# CurrentSense.net
KiCad netlist of a schematic drawn in Altium Designer
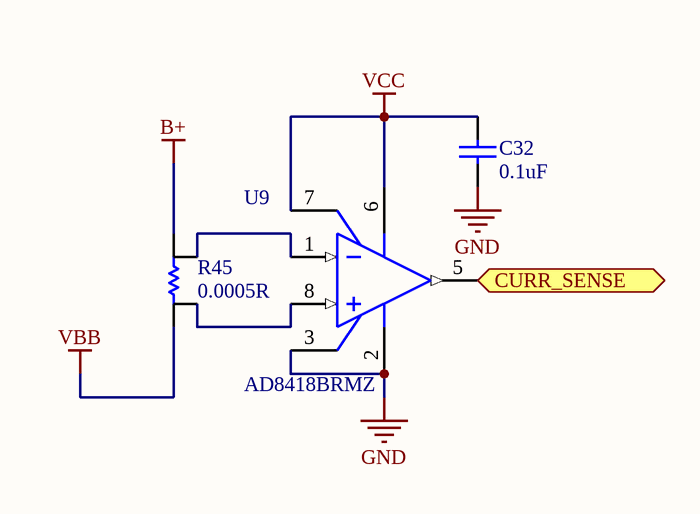
[diagram p0: CurrentSense.SchDoc]

(export (version "E")
  (design (tool "Eeschema 10.0.6"))
  (components
    (comp (ref "C32")
      (value "0.1uF")
      (footprint "C0402[1005X55]")
      (description "0.1uF 6.3V 10% 0402 (1005 Metric)")
      (fields (field (name "TOLERANCE") "10%") (field (name "PARTNUMBER") "GRM155R70J104KA01D"))
      (libsource (lib "Capacitors") (part "CAP_0.1uF_6.3V_0402_10%"))
    )
    (comp (ref "R45")
      (value "0.0005R")
      (footprint "WSL2726")
      (description "Current Sense Resistor, 0.0005R")
      (fields (field (name "PARTNUMBER") "WSLP2726L5000FEA") (field (name "MANUFACTURER") "Vishay / Dale"))
      (libsource (lib "Components") (part "WSLP2726"))
    )
    (comp (ref "U9")
      (value "AD8418BRMZ")
      (footprint "MSOP-8")
      (description "Current Sense Amplifiers Zero Drift ,Precision Current Sense AMP")
      (fields (field (name "MANUFACTURER") "Analog Devices"))
      (libsource (lib "ICs") (part "AD8418BRMZ"))
    )
  )
  (nets
    (net (code "1") (name "/CURR_SENSE") (class "Default")
      (node (ref "U9") (pin "5") (pinfunction "OUT_5") (pintype "output"))
    )
    (net (code "2") (name "B+") (class "Default")
      (node (ref "R45") (pin "2") (pinfunction "2_2") (pintype "passive"))
    )
    (net (code "3") (name "GND") (class "Default")
      (node (ref "C32") (pin "1") (pinfunction "1_1") (pintype "passive"))
      (node (ref "U9") (pin "2") (pinfunction "GND_2") (pintype "power_in"))
      (node (ref "U9") (pin "3") (pinfunction "VREF2_3") (pintype "passive"))
    )
    (net (code "4") (name "Net-(U9-IN+)") (class "Default")
      (node (ref "R45") (pin "3") (pinfunction "3_3") (pintype "passive"))
      (node (ref "U9") (pin "8") (pinfunction "IN+_8") (pintype "input"))
    )
    (net (code "5") (name "Net-(U9-IN-)") (class "Default")
      (node (ref "R45") (pin "4") (pinfunction "4_4") (pintype "passive"))
      (node (ref "U9") (pin "1") (pinfunction "IN-_1") (pintype "input"))
    )
    (net (code "6") (name "VBB") (class "Default")
      (node (ref "R45") (pin "1") (pinfunction "1_1") (pintype "passive"))
    )
    (net (code "7") (name "VCC") (class "Default")
      (node (ref "C32") (pin "2") (pinfunction "2_2") (pintype "passive"))
      (node (ref "U9") (pin "6") (pinfunction "VS_6") (pintype "power_in"))
      (node (ref "U9") (pin "7") (pinfunction "VREF1_7") (pintype "passive"))
    )
  )
)
